# powerRegulator.net
KiCad netlist of a schematic drawn in Altium Designer
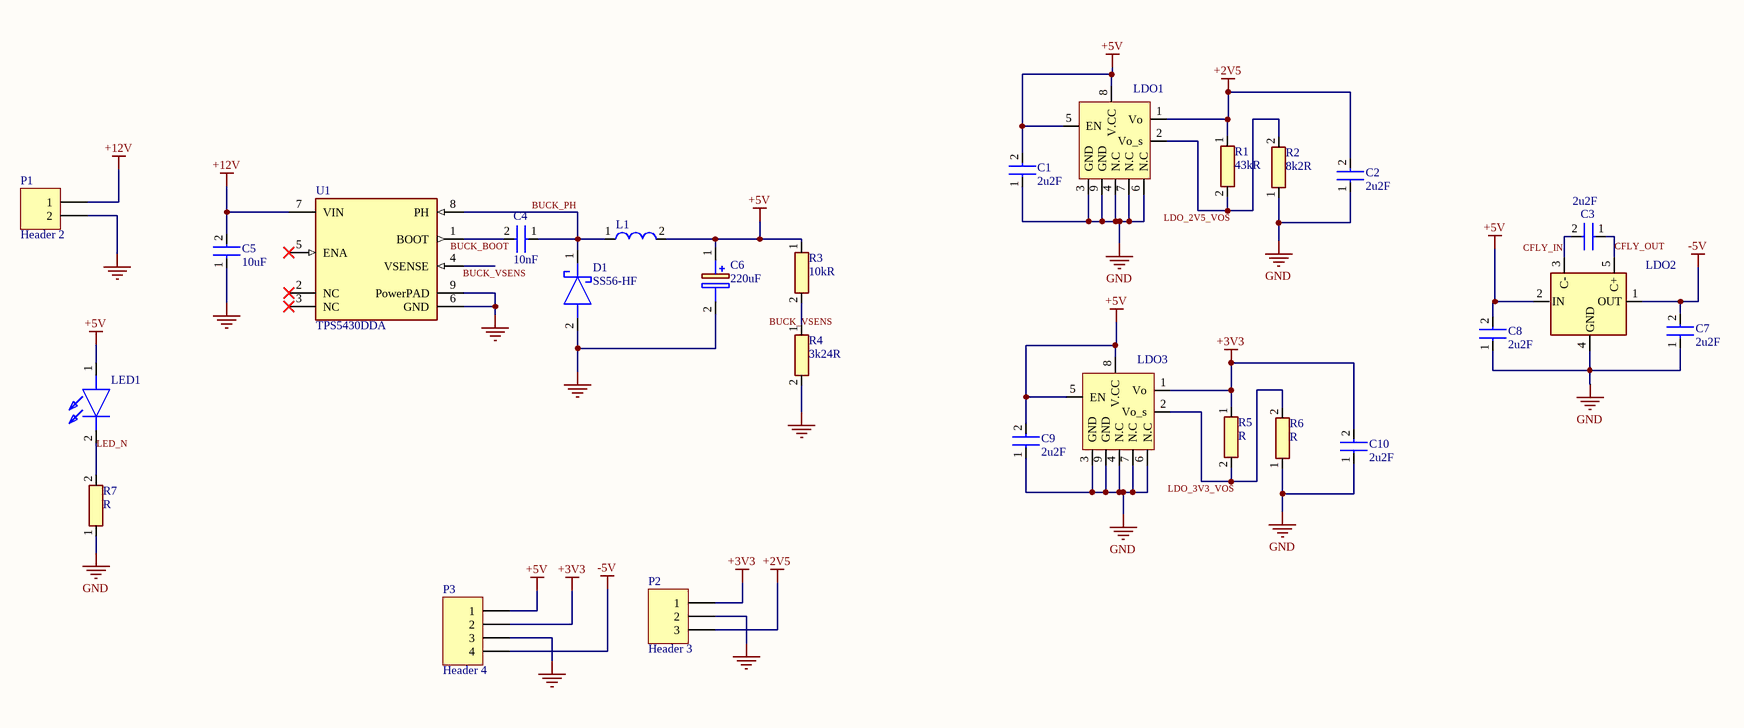
[diagram p0: powerRegulator.SchDoc]

(export (version "E")
  (design (tool "Eeschema 10.0.6"))
  (components
    (comp (ref "C1")
      (value "2u2F")
      (footprint "accessPoint:0603")
      (libsource (lib "accessPoint") (part "0603C"))
    )
    (comp (ref "C2")
      (value "2u2F")
      (footprint "accessPoint:0603")
      (libsource (lib "accessPoint") (part "0603C"))
    )
    (comp (ref "C3")
      (value "2u2F")
      (footprint "accessPoint:0603")
      (libsource (lib "accessPoint") (part "0603C"))
    )
    (comp (ref "C4")
      (value "10nF")
      (footprint "accessPoint:0603")
      (libsource (lib "accessPoint") (part "0603C"))
    )
    (comp (ref "C5")
      (value "10uF")
      (footprint "accessPoint:0603")
      (libsource (lib "accessPoint") (part "0603C"))
    )
    (comp (ref "C6")
      (value "220uF")
      (footprint "accessPoint:SMD_Electro_Cap")
      (description "Capacitor Polarised")
      (fields
        (field (name "MANUFACTURER_PART_NUMBER") "16SVPG270MX")
        (field (name "MOUSER PART NUMBER") "667-16SVPG270MX")
      )
      (libsource (lib "accessPoint") (part "SMD_Electro_Cap"))
    )
    (comp (ref "C7")
      (value "2u2F")
      (footprint "accessPoint:0603")
      (libsource (lib "accessPoint") (part "0603C"))
    )
    (comp (ref "C8")
      (value "2u2F")
      (footprint "accessPoint:0603")
      (libsource (lib "accessPoint") (part "0603C"))
    )
    (comp (ref "C9")
      (value "2u2F")
      (footprint "accessPoint:0603")
      (libsource (lib "accessPoint") (part "0603C"))
    )
    (comp (ref "C10")
      (value "2u2F")
      (footprint "accessPoint:0603")
      (libsource (lib "accessPoint") (part "0603C"))
    )
    (comp (ref "D1")
      (value "SS56-HF")
      (footprint "SamacSys:DIOM5025X220N")
      (description "Schottky Diode")
      (fields (field (name "MOUSER PART NUMBER") "750-SS56-HF"))
      (libsource (lib "*") (part "SS56-HF"))
    )
    (comp (ref "L1")
      (value "Inductor")
      (footprint "accessPoint:INDP120120X80N")
      (description "Inductor Power Shielded Wirewound 470uH 10% 1KHz 18Q-Factor Ferrite 0.18A 3.3Ohm DCR T/R")
      (fields
        (field (name "MANUFACTURER") "Bourns")
        (field (name "MANUFACTURER PART NUMBER") "SRR0604-471KL")
      )
      (libsource (lib "accessPoint") (part "33uH"))
    )
    (comp (ref "LDO1")
      (value "LDO")
      (footprint "accessPoint:LDO")
      (description "IC REG LDO ADJ 0.3A 8VSON")
      (fields (field (name "MANUFACTURER") "Rohm") (field (name "MANUFACTURER PART NUMBER") "BD00GA3WNUX-TR"))
      (libsource (lib "accessPoint") (part "LDO"))
    )
    (comp (ref "LDO2")
      (value "-5V LDO")
      (footprint "accessPoint:-5v_TPS60400DBVR")
      (description "Integrated Circuit")
      (fields
        (field (name "MANUFACTURER_PART_NUMBER") "TPS60400DBVR")
        (field (name "MOUSER PART NUMBER") "595-TPS60400DBVR")
      )
      (libsource (lib "accessPoint") (part "-5V LDO"))
    )
    (comp (ref "LDO3")
      (value "LDO")
      (footprint "accessPoint:LDO")
      (description "IC REG LDO ADJ 0.3A 8VSON")
      (fields (field (name "MANUFACTURER") "Rohm") (field (name "MANUFACTURER PART NUMBER") "BD00GA3WNUX-TR"))
      (libsource (lib "accessPoint") (part "LDO"))
    )
    (comp (ref "LED1")
      (value "0603 LED Green")
      (footprint "accessPoint:0603 LED")
      (description "LED")
      (fields
        (field (name "MANUFACTURER_PART_NUMBER") "150060VS75003")
        (field (name "MOUSER PART NUMBER") "710-150060VS75003")
      )
      (libsource (lib "accessPoint") (part "0603 LED Green"))
    )
    (comp (ref "P1")
      (value "Header 2")
      (footprint "HDR1X2")
      (description "Header, 2-Pin")
      (fields (field (name "PUBLISHER") "Altium Limited"))
      (libsource (lib "Miscellaneous Connectors") (part "Header 2"))
    )
    (comp (ref "P2")
      (value "Header 3")
      (footprint "HDR1X3")
      (description "Header, 3-Pin")
      (fields (field (name "PUBLISHER") "Altium Limited"))
      (libsource (lib "Miscellaneous Connectors") (part "Header 3"))
    )
    (comp (ref "P3")
      (value "Header 4")
      (footprint "HDR1X4")
      (description "Header, 4-Pin")
      (fields (field (name "PUBLISHER") "Altium Limited"))
      (libsource (lib "Miscellaneous Connectors") (part "Header 4"))
    )
    (comp (ref "R1")
      (value "43kR")
      (footprint "accessPoint:0603")
      (libsource (lib "accessPoint") (part "0603R"))
    )
    (comp (ref "R2") (value "8k2R") (footprint "accessPoint:0603") (libsource (lib "") (part "0603R_1")))
    (comp (ref "R3")
      (value "10kR")
      (footprint "accessPoint:0603")
      (libsource (lib "accessPoint") (part "0603R"))
    )
    (comp (ref "R4")
      (value "3k24R")
      (footprint "accessPoint:0603")
      (libsource (lib "accessPoint") (part "0603R"))
    )
    (comp (ref "R5")
      (value "R")
      (footprint "accessPoint:0603")
      (libsource (lib "accessPoint") (part "0603R"))
    )
    (comp (ref "R6") (value "R") (footprint "accessPoint:0603") (libsource (lib "") (part "0603R_1")))
    (comp (ref "R7") (value "R") (footprint "accessPoint:0603") (libsource (lib "") (part "0603R_1")))
    (comp (ref "U1")
      (value "TPS5430DDA")
      (footprint "accessPoint:FP-DDA0008J-IPC_A")
      (description "IC REG BUCK ADJUSTABLE 3A 8SOPWR")
      (fields
        (field (name "MANUFACTURER") "Texas Instruments")
        (field (name "OCTOPART") "https://octopart.com/tps5430dda-texas+instruments-589977")
      )
      (libsource (lib "accessPoint") (part "BUCK_CMP-2000-04960-2"))
    )
  )
  (nets
    (net (code "1") (name "+2V5") (class "Default")
      (node (ref "C2") (pin "2") (pinfunction "2_2") (pintype "passive"))
      (node (ref "LDO1") (pin "1") (pinfunction "Vo_1") (pintype "passive"))
      (node (ref "P2") (pin "3") (pinfunction "3_3") (pintype "passive"))
      (node (ref "R1") (pin "1") (pinfunction "1_1") (pintype "passive"))
    )
    (net (code "2") (name "+3V3") (class "Default")
      (node (ref "C10") (pin "2") (pinfunction "2_2") (pintype "passive"))
      (node (ref "LDO3") (pin "1") (pinfunction "Vo_1") (pintype "passive"))
      (node (ref "P2") (pin "1") (pinfunction "1_1") (pintype "passive"))
      (node (ref "P3") (pin "2") (pinfunction "2_2") (pintype "passive"))
      (node (ref "R5") (pin "1") (pinfunction "1_1") (pintype "passive"))
    )
    (net (code "3") (name "+5V") (class "Default")
      (node (ref "C1") (pin "2") (pinfunction "2_2") (pintype "passive"))
      (node (ref "C6") (pin "1") (pinfunction "+_1") (pintype "passive"))
      (node (ref "C8") (pin "2") (pinfunction "2_2") (pintype "passive"))
      (node (ref "C9") (pin "2") (pinfunction "2_2") (pintype "passive"))
      (node (ref "L1") (pin "2") (pinfunction "2_2") (pintype "passive"))
      (node (ref "LDO1") (pin "5") (pinfunction "EN_5") (pintype "passive"))
      (node (ref "LDO1") (pin "8") (pinfunction "V.CC_8") (pintype "passive"))
      (node (ref "LDO2") (pin "2") (pinfunction "IN_2") (pintype "passive"))
      (node (ref "LDO3") (pin "5") (pinfunction "EN_5") (pintype "passive"))
      (node (ref "LDO3") (pin "8") (pinfunction "V.CC_8") (pintype "passive"))
      (node (ref "LED1") (pin "1") (pinfunction "A_1") (pintype "passive"))
      (node (ref "P3") (pin "1") (pinfunction "1_1") (pintype "passive"))
      (node (ref "R3") (pin "1") (pinfunction "1_1") (pintype "passive"))
    )
    (net (code "4") (name "+12V") (class "Default")
      (node (ref "C5") (pin "2") (pinfunction "2_2") (pintype "passive"))
      (node (ref "P1") (pin "1") (pinfunction "1_1") (pintype "passive"))
      (node (ref "U1") (pin "7") (pinfunction "VIN_7") (pintype "power_in"))
    )
    (net (code "5") (name "-5V") (class "Default")
      (node (ref "C7") (pin "2") (pinfunction "2_2") (pintype "passive"))
      (node (ref "LDO2") (pin "1") (pinfunction "OUT_1") (pintype "passive"))
      (node (ref "P3") (pin "4") (pinfunction "4_4") (pintype "passive"))
    )
    (net (code "6") (name "/BUCK_BOOT") (class "Default")
      (node (ref "C4") (pin "2") (pinfunction "2_2") (pintype "passive"))
      (node (ref "U1") (pin "1") (pinfunction "BOOT_1") (pintype "output"))
    )
    (net (code "7") (name "/BUCK_PH") (class "Default")
      (node (ref "C4") (pin "1") (pinfunction "1_1") (pintype "passive"))
      (node (ref "D1") (pin "1") (pinfunction "K_1") (pintype "passive"))
      (node (ref "L1") (pin "1") (pinfunction "1_1") (pintype "passive"))
      (node (ref "U1") (pin "8") (pinfunction "PH_8") (pintype "input"))
    )
    (net (code "8") (name "/BUCK_VSENS") (class "Default")
      (node (ref "R3") (pin "2") (pinfunction "2_2") (pintype "passive"))
      (node (ref "R4") (pin "1") (pinfunction "1_1") (pintype "passive"))
      (node (ref "U1") (pin "4") (pinfunction "VSENSE_4") (pintype "input"))
    )
    (net (code "9") (name "/CFLY_IN") (class "Default")
      (node (ref "C3") (pin "2") (pinfunction "2_2") (pintype "passive"))
      (node (ref "LDO2") (pin "3") (pinfunction "C-_3") (pintype "passive"))
    )
    (net (code "10") (name "/CFLY_OUT") (class "Default")
      (node (ref "C3") (pin "1") (pinfunction "1_1") (pintype "passive"))
      (node (ref "LDO2") (pin "5") (pinfunction "C+_5") (pintype "passive"))
    )
    (net (code "11") (name "/LDO_2V5_VOS") (class "Default")
      (node (ref "LDO1") (pin "2") (pinfunction "Vo_s_2") (pintype "passive"))
      (node (ref "R1") (pin "2") (pinfunction "2_2") (pintype "passive"))
      (node (ref "R2") (pin "2") (pinfunction "2_2") (pintype "passive"))
    )
    (net (code "12") (name "/LDO_3V3_VOS") (class "Default")
      (node (ref "LDO3") (pin "2") (pinfunction "Vo_s_2") (pintype "passive"))
      (node (ref "R5") (pin "2") (pinfunction "2_2") (pintype "passive"))
      (node (ref "R6") (pin "2") (pinfunction "2_2") (pintype "passive"))
    )
    (net (code "13") (name "/LED_N") (class "Default")
      (node (ref "LED1") (pin "2") (pinfunction "K_2") (pintype "passive"))
      (node (ref "R7") (pin "2") (pinfunction "2_2") (pintype "passive"))
    )
    (net (code "14") (name "GND") (class "Default")
      (node (ref "C1") (pin "1") (pinfunction "1_1") (pintype "passive"))
      (node (ref "C10") (pin "1") (pinfunction "1_1") (pintype "passive"))
      (node (ref "C2") (pin "1") (pinfunction "1_1") (pintype "passive"))
      (node (ref "C5") (pin "1") (pinfunction "1_1") (pintype "passive"))
      (node (ref "C6") (pin "2") (pinfunction "-_2") (pintype "passive"))
      (node (ref "C7") (pin "1") (pinfunction "1_1") (pintype "passive"))
      (node (ref "C8") (pin "1") (pinfunction "1_1") (pintype "passive"))
      (node (ref "C9") (pin "1") (pinfunction "1_1") (pintype "passive"))
      (node (ref "D1") (pin "2") (pinfunction "A_2") (pintype "passive"))
      (node (ref "LDO1") (pin "3") (pinfunction "GND_3") (pintype "passive"))
      (node (ref "LDO1") (pin "4") (pinfunction "N.C_4") (pintype "passive"))
      (node (ref "LDO1") (pin "6") (pinfunction "N.C_6") (pintype "passive"))
      (node (ref "LDO1") (pin "7") (pinfunction "N.C_7") (pintype "passive"))
      (node (ref "LDO1") (pin "9") (pinfunction "GND_9") (pintype "passive"))
      (node (ref "LDO2") (pin "4") (pinfunction "GND_4") (pintype "passive"))
      (node (ref "LDO3") (pin "3") (pinfunction "GND_3") (pintype "passive"))
      (node (ref "LDO3") (pin "4") (pinfunction "N.C_4") (pintype "passive"))
      (node (ref "LDO3") (pin "6") (pinfunction "N.C_6") (pintype "passive"))
      (node (ref "LDO3") (pin "7") (pinfunction "N.C_7") (pintype "passive"))
      (node (ref "LDO3") (pin "9") (pinfunction "GND_9") (pintype "passive"))
      (node (ref "P1") (pin "2") (pinfunction "2_2") (pintype "passive"))
      (node (ref "P2") (pin "2") (pinfunction "2_2") (pintype "passive"))
      (node (ref "P3") (pin "3") (pinfunction "3_3") (pintype "passive"))
      (node (ref "R2") (pin "1") (pinfunction "1_1") (pintype "passive"))
      (node (ref "R4") (pin "2") (pinfunction "2_2") (pintype "passive"))
      (node (ref "R6") (pin "1") (pinfunction "1_1") (pintype "passive"))
      (node (ref "R7") (pin "1") (pinfunction "1_1") (pintype "passive"))
      (node (ref "U1") (pin "6") (pinfunction "GND_6") (pintype "power_in"))
      (node (ref "U1") (pin "9") (pinfunction "PowerPAD_9") (pintype "power_in"))
    )
    (net (code "15") (name "unconnected-(U1-ENA-Pad5)") (class "Default")
      (node (ref "U1") (pin "5") (pinfunction "ENA_5") (pintype "input+no_connect"))
    )
    (net (code "16") (name "unconnected-(U1-NC-Pad2)") (class "Default")
      (node (ref "U1") (pin "2") (pinfunction "NC_2") (pintype "passive+no_connect"))
    )
    (net (code "17") (name "unconnected-(U1-NC-Pad3)") (class "Default")
      (node (ref "U1") (pin "3") (pinfunction "NC_3") (pintype "passive+no_connect"))
    )
  )
)
